# PCB_Guardian.net
KiCad netlist of a schematic drawn in Altium Designer
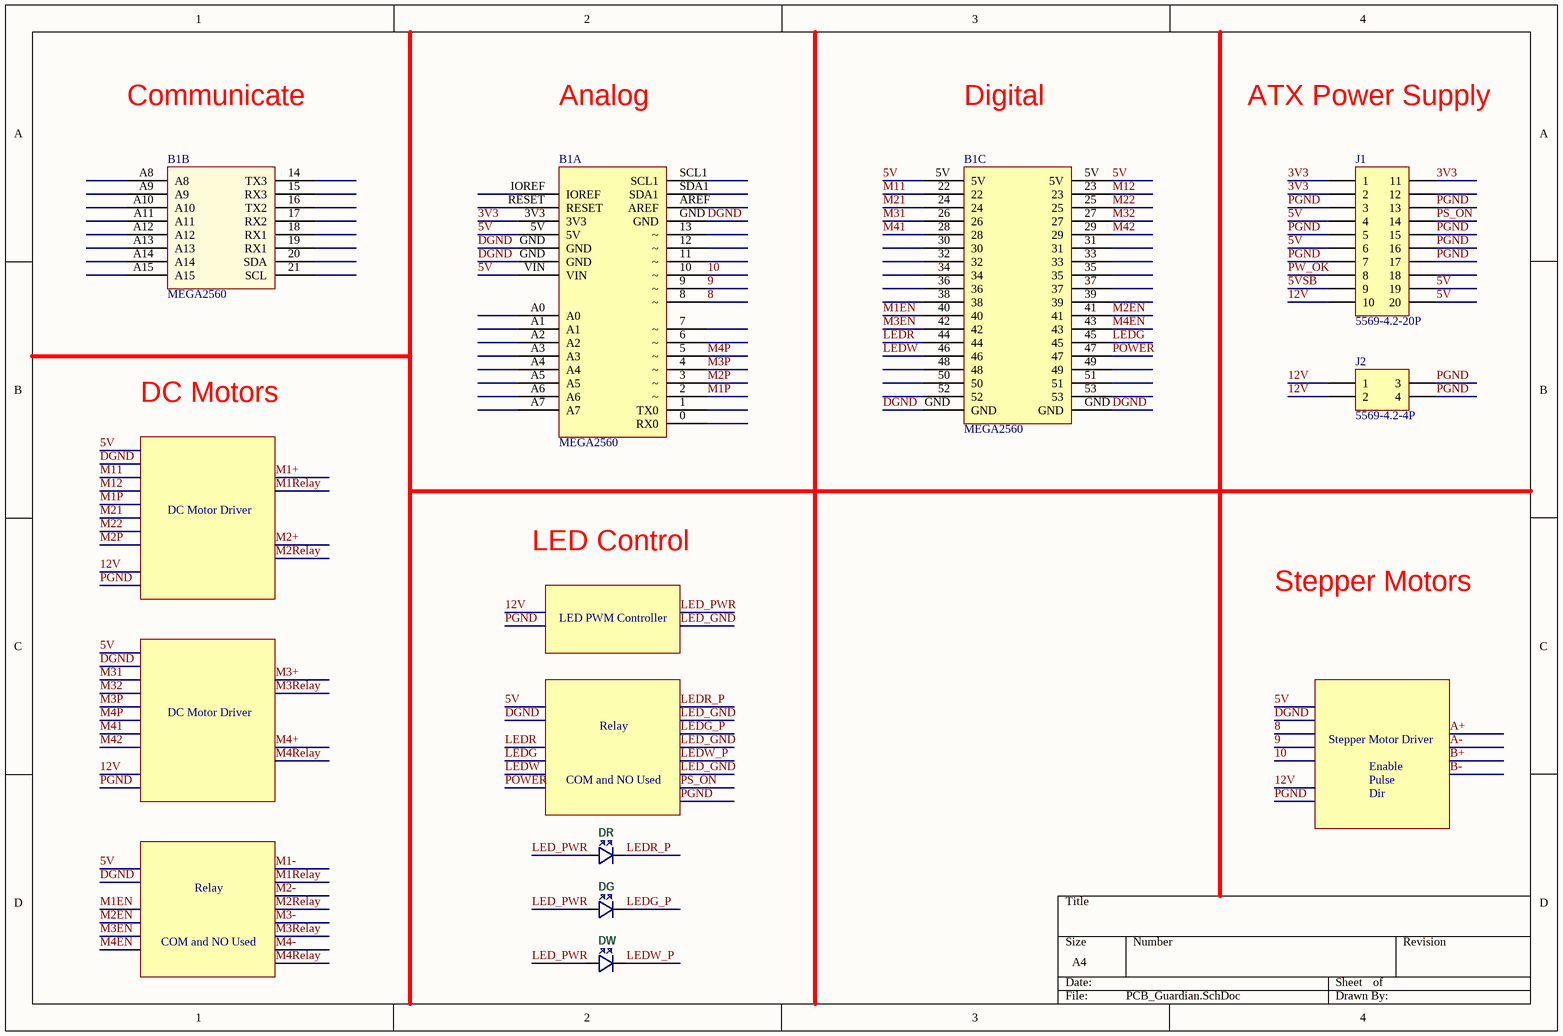
[diagram p0: PCB_Guardian.SchDoc]

(export (version "E")
  (design (tool "Eeschema 10.0.6"))
  (components
    (comp (ref "B1")
      (value "MEGA2560")
      (footprint "Arduino MEGA2560 Center Mount Holes")
      (libsource (lib "Arduino UNO & MEGA2560") (part "Arduino"))
    )
    (comp (ref "DG") (value "~") (description "=Description") (libsource (lib "LED") (part "LED")))
    (comp (ref "DR") (value "~") (description "=Description") (libsource (lib "LED") (part "LED")))
    (comp (ref "DW") (value "~") (description "=Description") (libsource (lib "LED") (part "LED")))
    (comp (ref "J1")
      (value "5569-4.2-20P")
      (footprint "Connector:5569_2*10P_CEN_H_4.2")
      (description "5557/5569母座")
      (libsource (lib "Connector") (part "5569-4.2-20P 弯脚"))
    )
    (comp (ref "J2")
      (value "5569-4.2-4P")
      (footprint "Connector:5569_2*2P_CEN_H_4.2")
      (description "5557/5569母座")
      (libsource (lib "Connector") (part "5569-4.2-4P 弯脚"))
    )
  )
  (nets
    (net (code "1") (name "/3V3") (class "Default")
      (node (ref "B1") (pin "3V3") (pinfunction "3V3_3V3") (pintype "passive"))
      (node (ref "J1") (pin "1") (pinfunction "1_1") (pintype "passive"))
      (node (ref "J1") (pin "11") (pinfunction "11_11") (pintype "passive"))
      (node (ref "J1") (pin "2") (pinfunction "2_2") (pintype "passive"))
    )
    (net (code "2") (name "/5V") (class "Default")
      (node (ref "B1") (pin "5V") (pinfunction "5V_5V") (pintype "passive"))
      (node (ref "B1") (pin "VIN") (pinfunction "VIN_VIN") (pintype "passive"))
      (node (ref "J1") (pin "19") (pinfunction "19_19") (pintype "passive"))
      (node (ref "J1") (pin "20") (pinfunction "20_20") (pintype "passive"))
      (node (ref "J1") (pin "4") (pinfunction "4_4") (pintype "passive"))
      (node (ref "J1") (pin "6") (pinfunction "6_6") (pintype "passive"))
    )
    (net (code "3") (name "/5VSB") (class "Default")
      (node (ref "J1") (pin "9") (pinfunction "9_9") (pintype "passive"))
    )
    (net (code "4") (name "/8") (class "Default")
      (node (ref "B1") (pin "8") (pinfunction "~_8") (pintype "passive"))
    )
    (net (code "5") (name "/9") (class "Default")
      (node (ref "B1") (pin "9") (pinfunction "~_9") (pintype "passive"))
    )
    (net (code "6") (name "/10") (class "Default")
      (node (ref "B1") (pin "10") (pinfunction "~_10") (pintype "passive"))
    )
    (net (code "7") (name "/12V") (class "Default")
      (node (ref "J1") (pin "10") (pinfunction "10_10") (pintype "passive"))
      (node (ref "J2") (pin "1") (pinfunction "1_1") (pintype "passive"))
      (node (ref "J2") (pin "2") (pinfunction "2_2") (pintype "passive"))
    )
    (net (code "12") (name "/DGND") (class "Default")
      (node (ref "B1") (pin "GND") (pinfunction "GND_GND") (pintype "passive"))
    )
    (net (code "13") (name "/LEDG") (class "Default")
      (node (ref "B1") (pin "45") (pinfunction "45_45") (pintype "passive"))
    )
    (net (code "14") (name "/LEDG_P") (class "Default") (node (ref "DG") (pin "K") (pintype "passive")))
    (net (code "15") (name "/LEDR") (class "Default")
      (node (ref "B1") (pin "44") (pinfunction "44_44") (pintype "passive"))
    )
    (net (code "16") (name "/LEDR_P") (class "Default") (node (ref "DR") (pin "K") (pintype "passive")))
    (net (code "17") (name "/LEDW") (class "Default")
      (node (ref "B1") (pin "46") (pinfunction "46_46") (pintype "passive"))
    )
    (net (code "18") (name "/LEDW_P") (class "Default") (node (ref "DW") (pin "K") (pintype "passive")))
    (net (code "20") (name "/LED_PWR") (class "Default")
      (node (ref "DG") (pin "A") (pintype "passive"))
      (node (ref "DR") (pin "A") (pintype "passive"))
      (node (ref "DW") (pin "A") (pintype "passive"))
    )
    (net (code "23") (name "/M1EN") (class "Default")
      (node (ref "B1") (pin "40") (pinfunction "40_40") (pintype "passive"))
    )
    (net (code "24") (name "/M1P") (class "Default")
      (node (ref "B1") (pin "2") (pinfunction "~_2") (pintype "passive"))
    )
    (net (code "28") (name "/M2EN") (class "Default")
      (node (ref "B1") (pin "41") (pinfunction "41_41") (pintype "passive"))
    )
    (net (code "29") (name "/M2P") (class "Default")
      (node (ref "B1") (pin "3") (pinfunction "~_3") (pintype "passive"))
    )
    (net (code "33") (name "/M3EN") (class "Default")
      (node (ref "B1") (pin "42") (pinfunction "42_42") (pintype "passive"))
    )
    (net (code "34") (name "/M3P") (class "Default")
      (node (ref "B1") (pin "4") (pinfunction "~_4") (pintype "passive"))
    )
    (net (code "38") (name "/M4EN") (class "Default")
      (node (ref "B1") (pin "43") (pinfunction "43_43") (pintype "passive"))
    )
    (net (code "39") (name "/M4P") (class "Default")
      (node (ref "B1") (pin "5") (pinfunction "~_5") (pintype "passive"))
    )
    (net (code "41") (name "/M11") (class "Default")
      (node (ref "B1") (pin "22") (pinfunction "22_22") (pintype "passive"))
    )
    (net (code "42") (name "/M12") (class "Default")
      (node (ref "B1") (pin "23") (pinfunction "23_23") (pintype "passive"))
    )
    (net (code "43") (name "/M21") (class "Default")
      (node (ref "B1") (pin "24") (pinfunction "24_24") (pintype "passive"))
    )
    (net (code "44") (name "/M22") (class "Default")
      (node (ref "B1") (pin "25") (pinfunction "25_25") (pintype "passive"))
    )
    (net (code "45") (name "/M31") (class "Default")
      (node (ref "B1") (pin "26") (pinfunction "26_26") (pintype "passive"))
    )
    (net (code "46") (name "/M32") (class "Default")
      (node (ref "B1") (pin "27") (pinfunction "27_27") (pintype "passive"))
    )
    (net (code "47") (name "/M41") (class "Default")
      (node (ref "B1") (pin "28") (pinfunction "28_28") (pintype "passive"))
    )
    (net (code "48") (name "/M42") (class "Default")
      (node (ref "B1") (pin "29") (pinfunction "29_29") (pintype "passive"))
    )
    (net (code "49") (name "/PGND") (class "Default")
      (node (ref "J1") (pin "13") (pinfunction "13_13") (pintype "passive"))
      (node (ref "J1") (pin "15") (pinfunction "15_15") (pintype "passive"))
      (node (ref "J1") (pin "16") (pinfunction "16_16") (pintype "passive"))
      (node (ref "J1") (pin "17") (pinfunction "17_17") (pintype "passive"))
      (node (ref "J1") (pin "3") (pinfunction "3_3") (pintype "passive"))
      (node (ref "J1") (pin "5") (pinfunction "5_5") (pintype "passive"))
      (node (ref "J1") (pin "7") (pinfunction "7_7") (pintype "passive"))
      (node (ref "J2") (pin "3") (pinfunction "3_3") (pintype "passive"))
      (node (ref "J2") (pin "4") (pinfunction "4_4") (pintype "passive"))
    )
    (net (code "50") (name "/POWER") (class "Default")
      (node (ref "B1") (pin "47") (pinfunction "47_47") (pintype "passive"))
    )
    (net (code "51") (name "/PS_ON") (class "Default")
      (node (ref "J1") (pin "14") (pinfunction "14_14") (pintype "passive"))
    )
    (net (code "52") (name "/PW_OK") (class "Default")
      (node (ref "J1") (pin "8") (pinfunction "8_8") (pintype "passive"))
    )
    (net (code "53") (name "unconnected-(B1-Pad30)") (class "Default")
      (node (ref "B1") (pin "30") (pinfunction "30_30") (pintype "passive"))
    )
    (net (code "54") (name "unconnected-(B1-Pad31)") (class "Default")
      (node (ref "B1") (pin "31") (pinfunction "31_31") (pintype "passive"))
    )
    (net (code "55") (name "unconnected-(B1-Pad32)") (class "Default")
      (node (ref "B1") (pin "32") (pinfunction "32_32") (pintype "passive"))
    )
    (net (code "56") (name "unconnected-(B1-Pad33)") (class "Default")
      (node (ref "B1") (pin "33") (pinfunction "33_33") (pintype "passive"))
    )
    (net (code "57") (name "unconnected-(B1-Pad34)") (class "Default")
      (node (ref "B1") (pin "34") (pinfunction "34_34") (pintype "passive"))
    )
    (net (code "58") (name "unconnected-(B1-Pad35)") (class "Default")
      (node (ref "B1") (pin "35") (pinfunction "35_35") (pintype "passive"))
    )
    (net (code "59") (name "unconnected-(B1-Pad36)") (class "Default")
      (node (ref "B1") (pin "36") (pinfunction "36_36") (pintype "passive"))
    )
    (net (code "60") (name "unconnected-(B1-Pad37)") (class "Default")
      (node (ref "B1") (pin "37") (pinfunction "37_37") (pintype "passive"))
    )
    (net (code "61") (name "unconnected-(B1-Pad38)") (class "Default")
      (node (ref "B1") (pin "38") (pinfunction "38_38") (pintype "passive"))
    )
    (net (code "62") (name "unconnected-(B1-Pad39)") (class "Default")
      (node (ref "B1") (pin "39") (pinfunction "39_39") (pintype "passive"))
    )
    (net (code "63") (name "unconnected-(B1-Pad48)") (class "Default")
      (node (ref "B1") (pin "48") (pinfunction "48_48") (pintype "passive"))
    )
    (net (code "64") (name "unconnected-(B1-Pad49)") (class "Default")
      (node (ref "B1") (pin "49") (pinfunction "49_49") (pintype "passive"))
    )
    (net (code "65") (name "unconnected-(B1-Pad50)") (class "Default")
      (node (ref "B1") (pin "50") (pinfunction "50_50") (pintype "passive"))
    )
    (net (code "66") (name "unconnected-(B1-Pad51)") (class "Default")
      (node (ref "B1") (pin "51") (pinfunction "51_51") (pintype "passive"))
    )
    (net (code "67") (name "unconnected-(B1-Pad52)") (class "Default")
      (node (ref "B1") (pin "52") (pinfunction "52_52") (pintype "passive"))
    )
    (net (code "68") (name "unconnected-(B1-Pad53)") (class "Default")
      (node (ref "B1") (pin "53") (pinfunction "53_53") (pintype "passive"))
    )
    (net (code "69") (name "unconnected-(B1-PadA0)") (class "Default")
      (node (ref "B1") (pin "A0") (pinfunction "A0_A0") (pintype "passive"))
    )
    (net (code "70") (name "unconnected-(B1-PadA1)") (class "Default")
      (node (ref "B1") (pin "A1") (pinfunction "A1_A1") (pintype "passive"))
    )
    (net (code "71") (name "unconnected-(B1-PadA2)") (class "Default")
      (node (ref "B1") (pin "A2") (pinfunction "A2_A2") (pintype "passive"))
    )
    (net (code "72") (name "unconnected-(B1-PadA3)") (class "Default")
      (node (ref "B1") (pin "A3") (pinfunction "A3_A3") (pintype "passive"))
    )
    (net (code "73") (name "unconnected-(B1-PadA4)") (class "Default")
      (node (ref "B1") (pin "A4") (pinfunction "A4_A4") (pintype "passive"))
    )
    (net (code "74") (name "unconnected-(B1-PadA5)") (class "Default")
      (node (ref "B1") (pin "A5") (pinfunction "A5_A5") (pintype "passive"))
    )
    (net (code "75") (name "unconnected-(B1-PadA6)") (class "Default")
      (node (ref "B1") (pin "A6") (pinfunction "A6_A6") (pintype "passive"))
    )
    (net (code "76") (name "unconnected-(B1-PadA7)") (class "Default")
      (node (ref "B1") (pin "A7") (pinfunction "A7_A7") (pintype "passive"))
    )
    (net (code "77") (name "unconnected-(B1-PadA8)") (class "Default")
      (node (ref "B1") (pin "A8") (pinfunction "A8_A8") (pintype "passive"))
    )
    (net (code "78") (name "unconnected-(B1-PadA9)") (class "Default")
      (node (ref "B1") (pin "A9") (pinfunction "A9_A9") (pintype "passive"))
    )
    (net (code "79") (name "unconnected-(B1-PadA10)") (class "Default")
      (node (ref "B1") (pin "A10") (pinfunction "A10_A10") (pintype "passive"))
    )
    (net (code "80") (name "unconnected-(B1-PadA11)") (class "Default")
      (node (ref "B1") (pin "A11") (pinfunction "A11_A11") (pintype "passive"))
    )
    (net (code "81") (name "unconnected-(B1-PadA12)") (class "Default")
      (node (ref "B1") (pin "A12") (pinfunction "A12_A12") (pintype "passive"))
    )
    (net (code "82") (name "unconnected-(B1-PadA13)") (class "Default")
      (node (ref "B1") (pin "A13") (pinfunction "A13_A13") (pintype "passive"))
    )
    (net (code "83") (name "unconnected-(B1-PadA14)") (class "Default")
      (node (ref "B1") (pin "A14") (pinfunction "A14_A14") (pintype "passive"))
    )
    (net (code "84") (name "unconnected-(B1-PadA15)") (class "Default")
      (node (ref "B1") (pin "A15") (pinfunction "A15_A15") (pintype "passive"))
    )
    (net (code "85") (name "unconnected-(B1-PadAREF)") (class "Default")
      (node (ref "B1") (pin "AREF") (pinfunction "AREF_AREF") (pintype "passive"))
    )
    (net (code "86") (name "unconnected-(B1-PadIOREF)") (class "Default")
      (node (ref "B1") (pin "IOREF") (pinfunction "IOREF_IOREF") (pintype "passive"))
    )
    (net (code "87") (name "unconnected-(B1-PadRESET)") (class "Default")
      (node (ref "B1") (pin "RESET") (pinfunction "RESET_RESET") (pintype "passive"))
    )
    (net (code "88") (name "unconnected-(B1-PadSCL1)") (class "Default")
      (node (ref "B1") (pin "SCL1") (pinfunction "SCL1_SCL1") (pintype "passive"))
    )
    (net (code "89") (name "unconnected-(B1-PadSDA1)") (class "Default")
      (node (ref "B1") (pin "SDA1") (pinfunction "SDA1_SDA1") (pintype "passive"))
    )
    (net (code "90") (name "unconnected-(B1A-RX0-Pad0)") (class "Default")
      (node (ref "B1") (pin "0") (pinfunction "RX0_0") (pintype "passive"))
    )
    (net (code "91") (name "unconnected-(B1A-TX0-Pad1)") (class "Default")
      (node (ref "B1") (pin "1") (pinfunction "TX0_1") (pintype "passive"))
    )
    (net (code "92") (name "unconnected-(B1A-~-Pad6)") (class "Default")
      (node (ref "B1") (pin "6") (pinfunction "~_6") (pintype "passive"))
    )
    (net (code "93") (name "unconnected-(B1A-~-Pad7)") (class "Default")
      (node (ref "B1") (pin "7") (pinfunction "~_7") (pintype "passive"))
    )
    (net (code "94") (name "unconnected-(B1A-~-Pad11)") (class "Default")
      (node (ref "B1") (pin "11") (pinfunction "~_11") (pintype "passive"))
    )
    (net (code "95") (name "unconnected-(B1A-~-Pad12)") (class "Default")
      (node (ref "B1") (pin "12") (pinfunction "~_12") (pintype "passive"))
    )
    (net (code "96") (name "unconnected-(B1A-~-Pad13)") (class "Default")
      (node (ref "B1") (pin "13") (pinfunction "~_13") (pintype "passive"))
    )
    (net (code "97") (name "unconnected-(B1B-RX1-Pad18)") (class "Default")
      (node (ref "B1") (pin "18") (pinfunction "RX1_18") (pintype "passive"))
    )
    (net (code "98") (name "unconnected-(B1B-RX1-Pad19)") (class "Default")
      (node (ref "B1") (pin "19") (pinfunction "RX1_19") (pintype "passive"))
    )
    (net (code "99") (name "unconnected-(B1B-RX2-Pad17)") (class "Default")
      (node (ref "B1") (pin "17") (pinfunction "RX2_17") (pintype "passive"))
    )
    (net (code "100") (name "unconnected-(B1B-RX3-Pad15)") (class "Default")
      (node (ref "B1") (pin "15") (pinfunction "RX3_15") (pintype "passive"))
    )
    (net (code "101") (name "unconnected-(B1B-SCL-Pad21)") (class "Default")
      (node (ref "B1") (pin "21") (pinfunction "SCL_21") (pintype "passive"))
    )
    (net (code "102") (name "unconnected-(B1B-SDA-Pad20)") (class "Default")
      (node (ref "B1") (pin "20") (pinfunction "SDA_20") (pintype "passive"))
    )
    (net (code "103") (name "unconnected-(B1B-TX2-Pad16)") (class "Default")
      (node (ref "B1") (pin "16") (pinfunction "TX2_16") (pintype "passive"))
    )
    (net (code "104") (name "unconnected-(B1B-TX3-Pad14)") (class "Default")
      (node (ref "B1") (pin "14") (pinfunction "TX3_14") (pintype "passive"))
    )
    (net (code "105") (name "unconnected-(J1-Pad12)") (class "Default")
      (node (ref "J1") (pin "12") (pinfunction "12_12") (pintype "passive"))
    )
    (net (code "106") (name "unconnected-(J1-Pad18)") (class "Default")
      (node (ref "J1") (pin "18") (pinfunction "18_18") (pintype "passive"))
    )
  )
)
